# High_Power_Output.net
KiCad netlist of a schematic drawn in Altium Designer
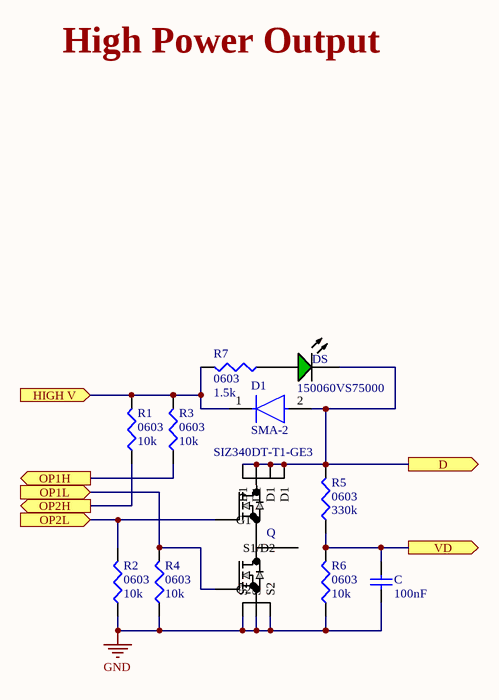
[diagram p0: High Power Output.SchDoc]

(export (version "E")
  (design (tool "Eeschema 10.0.6"))
  (components
    (comp (ref "C")
      (value "100nF")
      (footprint "CAPC1608X95X40ML15T15")
      (fields (field (name "MANUFACTURER") "Vitramon") (field (name "PART NUMBER") "VJ0603Y104KXQCW1BC"))
      (libsource (lib "Altium Content Vault") (part "CAP"))
    )
    (comp (ref "D1")
      (value "SMA-2")
      (footprint "FP-DO-214AC-MFG")
      (description "DIODE GEN PURP 1.6KV 1A DO214AC")
      (libsource (lib "Altium Content Vault") (part "d7152d700b627762746794eb795d46e"))
    )
    (comp (ref "DS")
      (value "150060VS75000")
      (footprint "WE-150060VS75000_V")
      (libsource (lib "Altium Content Vault") (part "LED_GREEN_K1A2-2"))
    )
    (comp (ref "Q")
      (value "SIZ340DT-T1-GE3")
      (footprint "MOSFET_DT-T1-GE3_VIS")
      (description "No Description Available")
      (fields (field (name "COPYRIGHT") "Copyright (C) 2022 Ultra Librarian. All rights reserved."))
      (libsource (lib "SIZ340DT-T1-GE3") (part "SIZ340DT-T1-GE3"))
    )
    (comp (ref "R1")
      (value "0603")
      (footprint "J1-0603")
      (description "Resistor")
      (fields (field (name "ALTIUM_VALUE") "10k") (field (name "PUBLISHER") "Altium Limited"))
      (libsource (lib "Miscellaneous Devices") (part "Res3"))
    )
    (comp (ref "R2")
      (value "0603")
      (footprint "J1-0603")
      (description "Resistor")
      (fields (field (name "ALTIUM_VALUE") "10k") (field (name "PUBLISHER") "Altium Limited"))
      (libsource (lib "Miscellaneous Devices") (part "Res3"))
    )
    (comp (ref "R3")
      (value "0603")
      (footprint "J1-0603")
      (description "Resistor")
      (fields (field (name "ALTIUM_VALUE") "10k") (field (name "PUBLISHER") "Altium Limited"))
      (libsource (lib "Miscellaneous Devices") (part "Res3"))
    )
    (comp (ref "R4")
      (value "0603")
      (footprint "J1-0603")
      (description "Resistor")
      (fields (field (name "ALTIUM_VALUE") "10k") (field (name "PUBLISHER") "Altium Limited"))
      (libsource (lib "Miscellaneous Devices") (part "Res3"))
    )
    (comp (ref "R5")
      (value "0603")
      (footprint "J1-0603")
      (description "Resistor")
      (fields (field (name "ALTIUM_VALUE") "330k") (field (name "PUBLISHER") "Altium Limited"))
      (libsource (lib "Miscellaneous Devices") (part "Res3"))
    )
    (comp (ref "R6")
      (value "0603")
      (footprint "J1-0603")
      (description "Resistor")
      (fields (field (name "ALTIUM_VALUE") "10k") (field (name "PUBLISHER") "Altium Limited"))
      (libsource (lib "Miscellaneous Devices") (part "Res3"))
    )
    (comp (ref "R7")
      (value "0603")
      (footprint "J1-0603")
      (description "Resistor")
      (fields (field (name "ALTIUM_VALUE") "1.5k") (field (name "PUBLISHER") "Altium Limited"))
      (libsource (lib "Miscellaneous Devices") (part "Res3"))
    )
  )
  (nets
    (net (code "1") (name "/D") (class "Default")
      (node (ref "D1") (pin "2") (pinfunction "A_2") (pintype "passive"))
      (node (ref "DS") (pin "1") (pinfunction "K_1") (pintype "passive"))
      (node (ref "Q") (pin "10") (pinfunction "D1_10") (pintype "bidirectional"))
      (node (ref "Q") (pin "2") (pinfunction "D1_2") (pintype "bidirectional"))
      (node (ref "Q") (pin "3") (pinfunction "D1_3") (pintype "bidirectional"))
      (node (ref "Q") (pin "4") (pinfunction "D1_4") (pintype "bidirectional"))
      (node (ref "R5") (pin "2") (pinfunction "2_2") (pintype "passive"))
    )
    (net (code "2") (name "/HIGH V") (class "Default")
      (node (ref "D1") (pin "1") (pinfunction "C_1") (pintype "passive"))
      (node (ref "R1") (pin "2") (pinfunction "2_2") (pintype "passive"))
      (node (ref "R3") (pin "2") (pinfunction "2_2") (pintype "passive"))
      (node (ref "R7") (pin "2") (pinfunction "2_2") (pintype "passive"))
    )
    (net (code "3") (name "/OP1H") (class "Default")
      (node (ref "R3") (pin "1") (pinfunction "1_1") (pintype "passive"))
    )
    (net (code "4") (name "/OP1L") (class "Default")
      (node (ref "Q") (pin "8") (pinfunction "G2_8") (pintype "bidirectional"))
      (node (ref "R4") (pin "2") (pinfunction "2_2") (pintype "passive"))
    )
    (net (code "5") (name "/OP2H") (class "Default")
      (node (ref "R1") (pin "1") (pinfunction "1_1") (pintype "passive"))
    )
    (net (code "6") (name "/OP2L") (class "Default")
      (node (ref "Q") (pin "1") (pinfunction "G1_1") (pintype "bidirectional"))
      (node (ref "R2") (pin "2") (pinfunction "2_2") (pintype "passive"))
    )
    (net (code "7") (name "/VD") (class "Default")
      (node (ref "C") (pin "2") (pinfunction "2_2") (pintype "passive"))
      (node (ref "R5") (pin "1") (pinfunction "1_1") (pintype "passive"))
      (node (ref "R6") (pin "2") (pinfunction "2_2") (pintype "passive"))
    )
    (net (code "8") (name "GND") (class "Default")
      (node (ref "C") (pin "1") (pinfunction "1_1") (pintype "passive"))
      (node (ref "Q") (pin "5") (pinfunction "S2_5") (pintype "bidirectional"))
      (node (ref "Q") (pin "6") (pinfunction "S2_6") (pintype "bidirectional"))
      (node (ref "Q") (pin "7") (pinfunction "S2_7") (pintype "passive"))
      (node (ref "R2") (pin "1") (pinfunction "1_1") (pintype "passive"))
      (node (ref "R4") (pin "1") (pinfunction "1_1") (pintype "passive"))
      (node (ref "R6") (pin "1") (pinfunction "1_1") (pintype "passive"))
    )
    (net (code "9") (name "Net-(DS-A)") (class "Default")
      (node (ref "DS") (pin "2") (pinfunction "A_2") (pintype "passive"))
      (node (ref "R7") (pin "1") (pinfunction "1_1") (pintype "passive"))
    )
    (net (code "10") (name "unconnected-(Q-S1{slash}D2-Pad9)") (class "Default")
      (node (ref "Q") (pin "9") (pinfunction "S1/D2_9") (pintype "bidirectional"))
    )
  )
)
